# Buck_and_LDO.net
KiCad netlist of a schematic drawn in Altium Designer
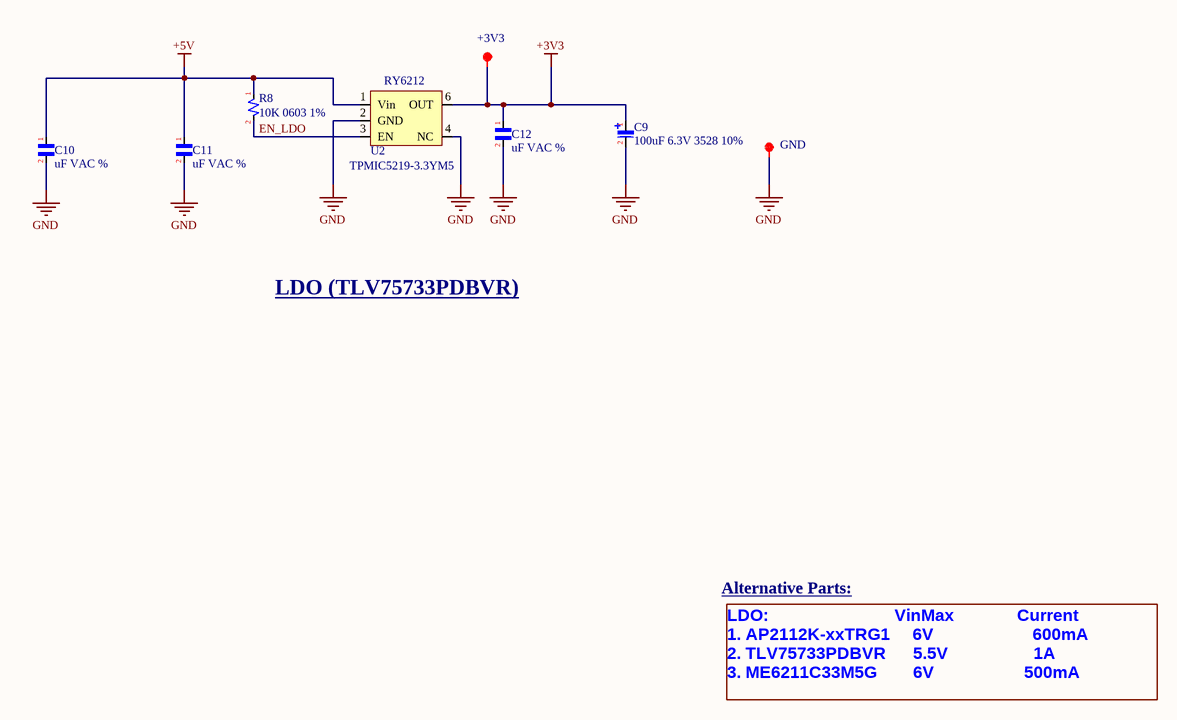
[diagram p0: Buck_and_LDO.SchDoc]

(export (version "E")
  (design (tool "Eeschema 10.0.6"))
  (components
    (comp (ref "C9")
      (value "100uF 6.3V 3528 10%")
      (footprint "CAPPC3528X210N")
      (libsource (lib "Walton_EED_13_05_2024") (part "Capacitor{gt}{gt} Polar"))
    )
    (comp (ref "C10")
      (value "uF VAC %")
      (footprint "C_X2_18X10X15.8_P15")
      (libsource (lib "Walton_EED_13_05_2024") (part "Capacitor{gt}{gt} Non-Polar"))
    )
    (comp (ref "C11")
      (value "uF VAC %")
      (footprint "C_X2_18X10X15.8_P15")
      (libsource (lib "Walton_EED_13_05_2024") (part "Capacitor{gt}{gt} Non-Polar"))
    )
    (comp (ref "C12")
      (value "uF VAC %")
      (footprint "C_X2_18X10X15.8_P15")
      (libsource (lib "Walton_EED_13_05_2024") (part "Capacitor{gt}{gt} Non-Polar"))
    )
    (comp (ref "R8")
      (value "10K 0603 1%")
      (footprint "R_0603")
      (description "RES 0603 20%")
      (libsource (lib "Walton_EED") (part "Resistor{gt}{gt} General Purpose"))
    )
    (comp (ref "TP5") (value "+3V3") (footprint "TP_1mm_SMD") (libsource (lib "*") (part "Test point TP")))
    (comp (ref "TP6") (value "GND") (footprint "TP_1mm_SMD") (libsource (lib "*") (part "Test point TP")))
    (comp (ref "U2")
      (value "RY6212 3V3 SOT23-5")
      (footprint "RY6212 SOT23-5")
      (description "The RY6212 highly accurate, low noise, CMOS LDO Voltage Regulators.")
      (libsource (lib "Walton_EED") (part "RY6212 3V3 SOT23-5"))
    )
  )
  (nets
    (net (code "1") (name "+3V3") (class "Default")
      (node (ref "C12") (pin "1") (pinfunction "1_1") (pintype "passive"))
      (node (ref "C9") (pin "1") (pinfunction "1_1") (pintype "passive"))
      (node (ref "TP5") (pin "1") (pinfunction "1_1") (pintype "passive"))
      (node (ref "U2") (pin "6") (pinfunction "OUT_6") (pintype "passive"))
    )
    (net (code "2") (name "+5V") (class "Default")
      (node (ref "C10") (pin "1") (pinfunction "1_1") (pintype "passive"))
      (node (ref "C11") (pin "1") (pinfunction "1_1") (pintype "passive"))
      (node (ref "R8") (pin "1") (pinfunction "1_1") (pintype "passive"))
      (node (ref "U2") (pin "1") (pinfunction "Vin_1") (pintype "passive"))
    )
    (net (code "3") (name "/EN_LDO") (class "Default")
      (node (ref "R8") (pin "2") (pinfunction "2_2") (pintype "passive"))
      (node (ref "U2") (pin "3") (pinfunction "EN_3") (pintype "passive"))
    )
    (net (code "4") (name "GND") (class "Default")
      (node (ref "C10") (pin "2") (pinfunction "2_2") (pintype "passive"))
      (node (ref "C11") (pin "2") (pinfunction "2_2") (pintype "passive"))
      (node (ref "C12") (pin "2") (pinfunction "2_2") (pintype "passive"))
      (node (ref "C9") (pin "2") (pinfunction "2_2") (pintype "passive"))
      (node (ref "TP6") (pin "1") (pinfunction "1_1") (pintype "passive"))
      (node (ref "U2") (pin "2") (pinfunction "GND_2") (pintype "passive"))
      (node (ref "U2") (pin "4") (pinfunction "NC_4") (pintype "passive"))
    )
  )
)
